# Sensor_Board_0x06_CO2_CCS811_v2.net
KiCad netlist of a schematic drawn in EAGLE
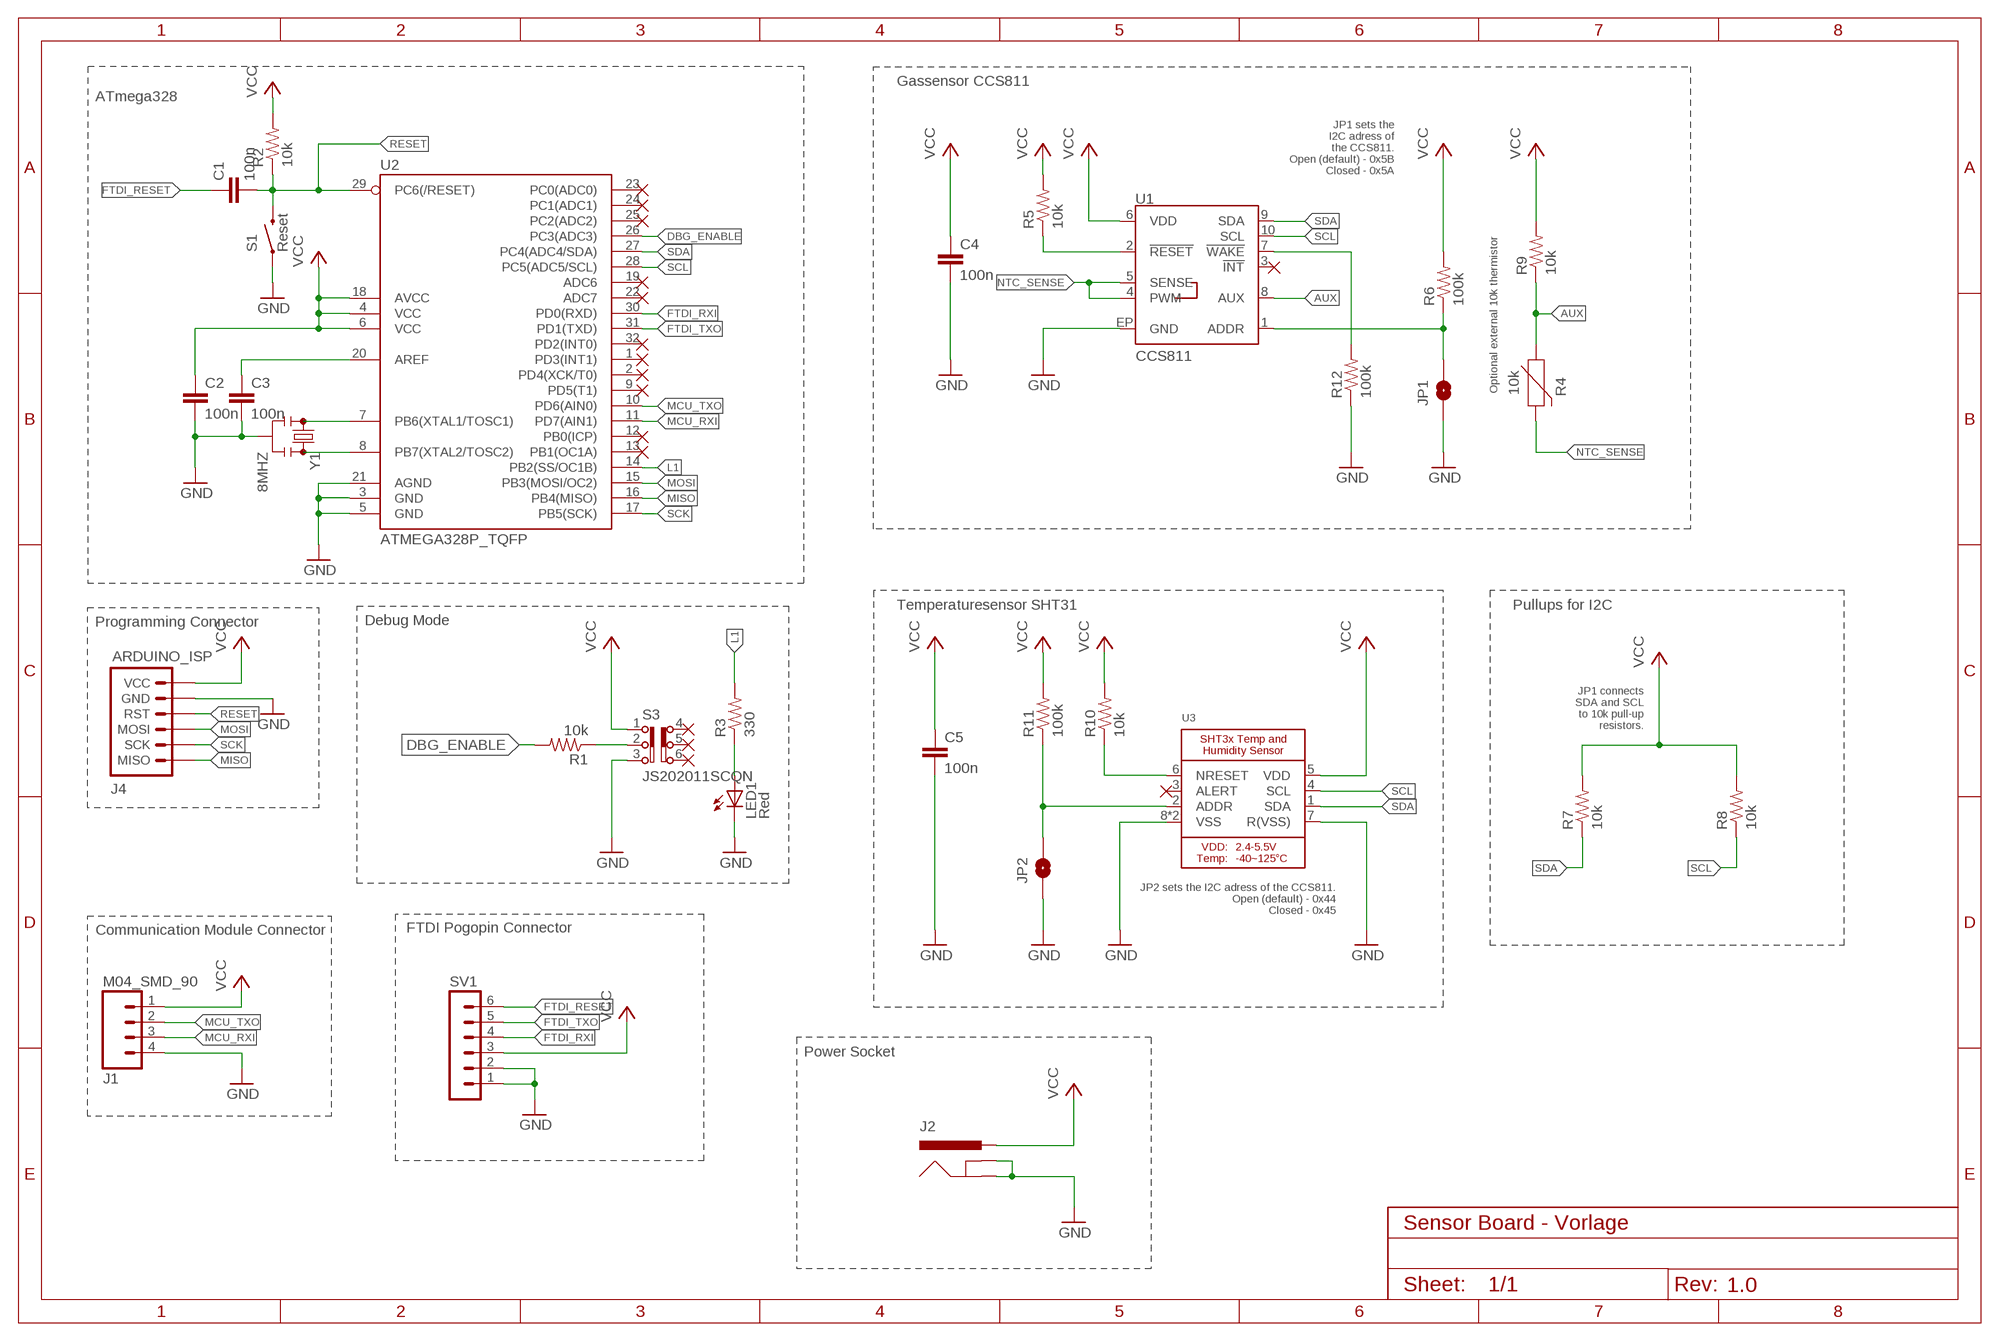
[diagram p0: schematic, sheet 1]

(export (version "E")
  (design (tool "Eeschema 10.0.6"))
  (components
    (comp (ref "C1")
      (value "100n")
      (footprint "eagle-import:C0805")
      (libsource (lib "eagle-import") (part "C"))
    )
    (comp (ref "C2")
      (value "100n")
      (footprint "eagle-import:C0805")
      (libsource (lib "eagle-import") (part "C"))
    )
    (comp (ref "C3")
      (value "100n")
      (footprint "eagle-import:C0805")
      (libsource (lib "eagle-import") (part "C"))
    )
    (comp (ref "C4")
      (value "100n")
      (footprint "eagle-import:C0805")
      (libsource (lib "eagle-import") (part "C"))
    )
    (comp (ref "C5")
      (value "100n")
      (footprint "eagle-import:C0805")
      (libsource (lib "eagle-import") (part "C"))
    )
    (comp (ref "J1")
      (value "M04_SMD_90")
      (footprint "eagle-import:M04_SMD_90")
      (libsource (lib "eagle-import") (part "M04_SMD_90"))
    )
    (comp (ref "J2")
      (value "5.5x2.1mm Barrel")
      (footprint "eagle-import:POWER_JACK_SMD")
      (libsource (lib "eagle-import") (part "POWER_JACKSMD"))
    )
    (comp (ref "J4")
      (value "ARDUINO_ISP")
      (footprint "eagle-import:M-2X3")
      (libsource (lib "eagle-import") (part "ARDUINO_ISP"))
    )
    (comp (ref "JP1")
      (value "SPARKFUN-JUMPERS_JUMPER-SMT_2_NO_SILK")
      (footprint "eagle-import:SPARKFUN-JUMPERS_SMT-JUMPER_2_NO_SILK")
      (libsource (lib "eagle-import") (part "SPARKFUN-JUMPERS_JUMPER-SMT_2_NO_SILK"))
    )
    (comp (ref "JP2")
      (value "SPARKFUN-JUMPERS_JUMPER-SMT_2_NO_SILK")
      (footprint "eagle-import:SPARKFUN-JUMPERS_SMT-JUMPER_2_NO_SILK")
      (libsource (lib "eagle-import") (part "SPARKFUN-JUMPERS_JUMPER-SMT_2_NO_SILK"))
    )
    (comp (ref "LED1")
      (value "Red")
      (footprint "eagle-import:SML0805")
      (libsource (lib "eagle-import") (part "LEDSML0805"))
    )
    (comp (ref "R1")
      (value "10k")
      (footprint "eagle-import:0805")
      (libsource (lib "eagle-import") (part "RESISTOR0805-RES"))
    )
    (comp (ref "R2")
      (value "10k")
      (footprint "eagle-import:0805")
      (libsource (lib "eagle-import") (part "RESISTOR0805-RES"))
    )
    (comp (ref "R3")
      (value "330")
      (footprint "eagle-import:0805")
      (libsource (lib "eagle-import") (part "RESISTOR0805-RES"))
    )
    (comp (ref "R4")
      (value "10k")
      (footprint "eagle-import:CCS811_BREAKOUT_TEMP_0603")
      (libsource (lib "eagle-import") (part "CCS811_BREAKOUT_TEMP_NTC-THERMISTOR-0603"))
    )
    (comp (ref "R5")
      (value "10k")
      (footprint "eagle-import:0805")
      (libsource (lib "eagle-import") (part "RESISTOR0805-RES"))
    )
    (comp (ref "R6")
      (value "100k")
      (footprint "eagle-import:0805")
      (libsource (lib "eagle-import") (part "RESISTOR0805-RES"))
    )
    (comp (ref "R7")
      (value "10k")
      (footprint "eagle-import:0805")
      (libsource (lib "eagle-import") (part "RESISTOR0805-RES"))
    )
    (comp (ref "R8")
      (value "10k")
      (footprint "eagle-import:0805")
      (libsource (lib "eagle-import") (part "RESISTOR0805-RES"))
    )
    (comp (ref "R9")
      (value "10k")
      (footprint "eagle-import:0805")
      (libsource (lib "eagle-import") (part "RESISTOR0805-RES"))
    )
    (comp (ref "R10")
      (value "10k")
      (footprint "eagle-import:0805")
      (libsource (lib "eagle-import") (part "RESISTOR0805-RES"))
    )
    (comp (ref "R11")
      (value "100k")
      (footprint "eagle-import:0805")
      (libsource (lib "eagle-import") (part "RESISTOR0805-RES"))
    )
    (comp (ref "R12")
      (value "100k")
      (footprint "eagle-import:0805")
      (libsource (lib "eagle-import") (part "RESISTOR0805-RES"))
    )
    (comp (ref "S1")
      (value "Reset")
      (footprint "eagle-import:M-PUSHBUTTON-SMD")
      (libsource (lib "eagle-import") (part "PUSHBUTTON"))
    )
    (comp (ref "S3")
      (value "JS202011SCQN")
      (footprint "eagle-import:JS202011SCQN")
      (libsource (lib "eagle-import") (part "JS202011SCQN"))
    )
    (comp (ref "SV1")
      (value "MA06-1")
      (footprint "eagle-import:MA06-1")
      (libsource (lib "eagle-import") (part "MA06-1"))
    )
    (comp (ref "U1")
      (value "CCS811")
      (footprint "eagle-import:CCS811_BREAKOUT_TEMP_LGA10")
      (libsource (lib "eagle-import") (part "CCS811_BREAKOUT_TEMP_CCS811"))
    )
    (comp (ref "U2")
      (value "ATMEGA328P_TQFP")
      (footprint "eagle-import:TQFP32-08")
      (libsource (lib "eagle-import") (part "ATMEGA328P_TQFP"))
    )
    (comp (ref "U3")
      (value "MICROBUILDER_SHT3X")
      (footprint "eagle-import:MICROBUILDER_SHT3X")
      (libsource (lib "eagle-import") (part "MICROBUILDER_SHT3X"))
    )
    (comp (ref "Y1")
      (value "8MHZ")
      (footprint "eagle-import:RESONATOR-SMD")
      (libsource (lib "eagle-import") (part "RESONATOR8MHZ"))
    )
  )
  (nets
    (net (code "1") (name "AUX") (class "Default")
      (node (ref "R4") (pin "1") (pinfunction "1_1") (pintype "bidirectional"))
      (node (ref "R9") (pin "1") (pinfunction "1_1") (pintype "passive"))
      (node (ref "U1") (pin "8") (pinfunction "AUX_8") (pintype "bidirectional"))
    )
    (net (code "2") (name "DBG_ENABLE") (class "Default")
      (node (ref "R1") (pin "2") (pinfunction "2_2") (pintype "passive"))
      (node (ref "U2") (pin "26") (pinfunction "PC3(ADC3)_26") (pintype "bidirectional"))
    )
    (net (code "3") (name "FTDI_RESET") (class "Default")
      (node (ref "C1") (pin "1") (pinfunction "1_1") (pintype "passive"))
      (node (ref "SV1") (pin "6") (pinfunction "6_6") (pintype "passive"))
    )
    (net (code "4") (name "FTDI_RXI") (class "Default")
      (node (ref "SV1") (pin "4") (pinfunction "4_4") (pintype "passive"))
      (node (ref "U2") (pin "30") (pinfunction "PD0(RXD)_30") (pintype "bidirectional"))
    )
    (net (code "5") (name "FTDI_TXO") (class "Default")
      (node (ref "SV1") (pin "5") (pinfunction "5_5") (pintype "passive"))
      (node (ref "U2") (pin "31") (pinfunction "PD1(TXD)_31") (pintype "bidirectional"))
    )
    (net (code "6") (name "GND") (class "Default")
      (node (ref "C2") (pin "2") (pinfunction "2_2") (pintype "passive"))
      (node (ref "C3") (pin "2") (pinfunction "2_2") (pintype "passive"))
      (node (ref "C4") (pin "2") (pinfunction "2_2") (pintype "passive"))
      (node (ref "C5") (pin "2") (pinfunction "2_2") (pintype "passive"))
      (node (ref "J1") (pin "4") (pinfunction "4_4") (pintype "passive"))
      (node (ref "J2") (pin "GND") (pinfunction "GNDBREAK_GND") (pintype "bidirectional"))
      (node (ref "J2") (pin "P$4") (pinfunction "GND_P$4") (pintype "bidirectional"))
      (node (ref "J4") (pin "P$5") (pinfunction "GND_P$5") (pintype "passive"))
      (node (ref "JP1") (pin "1") (pinfunction "1_1") (pintype "passive"))
      (node (ref "JP2") (pin "1") (pinfunction "1_1") (pintype "passive"))
      (node (ref "LED1") (pin "C") (pinfunction "C_C") (pintype "passive"))
      (node (ref "R12") (pin "1") (pinfunction "1_1") (pintype "passive"))
      (node (ref "S1") (pin "1") (pinfunction "LEFT_1") (pintype "passive"))
      (node (ref "S1") (pin "2") (pinfunction "LEFT_2") (pintype "passive"))
      (node (ref "S3") (pin "3") (pinfunction "3_3") (pintype "passive"))
      (node (ref "SV1") (pin "1") (pinfunction "1_1") (pintype "passive"))
      (node (ref "SV1") (pin "2") (pinfunction "2_2") (pintype "passive"))
      (node (ref "U1") (pin "EP") (pinfunction "GND_EP") (pintype "bidirectional"))
      (node (ref "U2") (pin "21") (pinfunction "AGND_21") (pintype "bidirectional"))
      (node (ref "U2") (pin "3") (pinfunction "GND_3") (pintype "bidirectional"))
      (node (ref "U2") (pin "5") (pinfunction "GND_5") (pintype "bidirectional"))
      (node (ref "U3") (pin "7") (pinfunction "R(VSS)_7") (pintype "bidirectional"))
      (node (ref "U3") (pin "8") (pinfunction "VSS_8") (pintype "power_in"))
      (node (ref "U3") (pin "THERMAL") (pinfunction "VSS_THERMAL") (pintype "power_in"))
      (node (ref "Y1") (pin "2") (pinfunction "2_2") (pintype "passive"))
    )
    (net (code "7") (name "L1") (class "Default")
      (node (ref "R3") (pin "2") (pinfunction "2_2") (pintype "passive"))
      (node (ref "U2") (pin "14") (pinfunction "PB2(SS/OC1B)_14") (pintype "bidirectional"))
    )
    (net (code "8") (name "MCU_RXI") (class "Default")
      (node (ref "J1") (pin "3") (pinfunction "3_3") (pintype "passive"))
      (node (ref "U2") (pin "11") (pinfunction "PD7(AIN1)_11") (pintype "bidirectional"))
    )
    (net (code "9") (name "MCU_TXO") (class "Default")
      (node (ref "J1") (pin "2") (pinfunction "2_2") (pintype "passive"))
      (node (ref "U2") (pin "10") (pinfunction "PD6(AIN0)_10") (pintype "bidirectional"))
    )
    (net (code "10") (name "MISO") (class "Default")
      (node (ref "J4") (pin "P$1") (pinfunction "MISO_P$1") (pintype "passive"))
      (node (ref "U2") (pin "16") (pinfunction "PB4(MISO)_16") (pintype "bidirectional"))
    )
    (net (code "11") (name "MOSI") (class "Default")
      (node (ref "J4") (pin "P$3") (pinfunction "MOSI_P$3") (pintype "passive"))
      (node (ref "U2") (pin "15") (pinfunction "PB3(MOSI/OC2)_15") (pintype "bidirectional"))
    )
    (net (code "12") (name "NTC_SENSE") (class "Default")
      (node (ref "R4") (pin "2") (pinfunction "2_2") (pintype "bidirectional"))
      (node (ref "U1") (pin "4") (pinfunction "PWM_4") (pintype "bidirectional"))
      (node (ref "U1") (pin "5") (pinfunction "SENSE_5") (pintype "bidirectional"))
    )
    (net (code "13") (name "Net-(LED1-PadA)") (class "Default")
      (node (ref "LED1") (pin "A") (pinfunction "A_A") (pintype "passive"))
      (node (ref "R3") (pin "1") (pinfunction "1_1") (pintype "passive"))
    )
    (net (code "14") (name "Net-(R1-Pad1)") (class "Default")
      (node (ref "R1") (pin "1") (pinfunction "1_1") (pintype "passive"))
      (node (ref "S3") (pin "2") (pinfunction "2_2") (pintype "passive"))
    )
    (net (code "15") (name "Net-(U1-ADDR)") (class "Default")
      (node (ref "JP1") (pin "2") (pinfunction "2_2") (pintype "passive"))
      (node (ref "R6") (pin "1") (pinfunction "1_1") (pintype "passive"))
      (node (ref "U1") (pin "1") (pinfunction "ADDR_1") (pintype "bidirectional"))
    )
    (net (code "16") (name "Net-(U1-~{RESET})") (class "Default")
      (node (ref "R5") (pin "1") (pinfunction "1_1") (pintype "passive"))
      (node (ref "U1") (pin "2") (pinfunction "~{RESET}_2") (pintype "bidirectional"))
    )
    (net (code "17") (name "Net-(U1-~{WAKE})") (class "Default")
      (node (ref "R12") (pin "2") (pinfunction "2_2") (pintype "passive"))
      (node (ref "U1") (pin "7") (pinfunction "~{WAKE}_7") (pintype "bidirectional"))
    )
    (net (code "18") (name "Net-(U2-AREF)") (class "Default")
      (node (ref "C3") (pin "1") (pinfunction "1_1") (pintype "passive"))
      (node (ref "U2") (pin "20") (pinfunction "AREF_20") (pintype "bidirectional"))
    )
    (net (code "19") (name "Net-(U2-PB6(XTAL1{slash}TOSC1))") (class "Default")
      (node (ref "U2") (pin "7") (pinfunction "PB6(XTAL1/TOSC1)_7") (pintype "bidirectional"))
      (node (ref "Y1") (pin "1") (pinfunction "1_1") (pintype "passive"))
    )
    (net (code "20") (name "Net-(U2-PB7(XTAL2{slash}TOSC2))") (class "Default")
      (node (ref "U2") (pin "8") (pinfunction "PB7(XTAL2/TOSC2)_8") (pintype "bidirectional"))
      (node (ref "Y1") (pin "3") (pinfunction "3_3") (pintype "passive"))
    )
    (net (code "21") (name "Net-(U3-ADDR)") (class "Default")
      (node (ref "JP2") (pin "2") (pinfunction "2_2") (pintype "passive"))
      (node (ref "R11") (pin "1") (pinfunction "1_1") (pintype "passive"))
      (node (ref "U3") (pin "2") (pinfunction "ADDR_2") (pintype "bidirectional"))
    )
    (net (code "22") (name "Net-(U3-NRESET)") (class "Default")
      (node (ref "R10") (pin "1") (pinfunction "1_1") (pintype "passive"))
      (node (ref "U3") (pin "6") (pinfunction "NRESET_6") (pintype "bidirectional"))
    )
    (net (code "23") (name "RESET") (class "Default")
      (node (ref "C1") (pin "2") (pinfunction "2_2") (pintype "passive"))
      (node (ref "J4") (pin "P$4") (pinfunction "RST_P$4") (pintype "passive"))
      (node (ref "R2") (pin "1") (pinfunction "1_1") (pintype "passive"))
      (node (ref "S1") (pin "3") (pinfunction "RIGHT_3") (pintype "passive"))
      (node (ref "S1") (pin "4") (pinfunction "RIGHT_4") (pintype "passive"))
      (node (ref "U2") (pin "29") (pinfunction "PC6(/RESET)_29") (pintype "bidirectional"))
    )
    (net (code "24") (name "SCK") (class "Default")
      (node (ref "J4") (pin "P$2") (pinfunction "SCK_P$2") (pintype "passive"))
      (node (ref "U2") (pin "17") (pinfunction "PB5(SCK)_17") (pintype "bidirectional"))
    )
    (net (code "25") (name "SCL") (class "Default")
      (node (ref "R8") (pin "1") (pinfunction "1_1") (pintype "passive"))
      (node (ref "U1") (pin "10") (pinfunction "SCL_10") (pintype "bidirectional"))
      (node (ref "U2") (pin "28") (pinfunction "PC5(ADC5/SCL)_28") (pintype "bidirectional"))
      (node (ref "U3") (pin "4") (pinfunction "SCL_4") (pintype "bidirectional"))
    )
    (net (code "26") (name "SDA") (class "Default")
      (node (ref "R7") (pin "1") (pinfunction "1_1") (pintype "passive"))
      (node (ref "U1") (pin "9") (pinfunction "SDA_9") (pintype "bidirectional"))
      (node (ref "U2") (pin "27") (pinfunction "PC4(ADC4/SDA)_27") (pintype "bidirectional"))
      (node (ref "U3") (pin "1") (pinfunction "SDA_1") (pintype "bidirectional"))
    )
    (net (code "27") (name "VCC") (class "Default")
      (node (ref "C2") (pin "1") (pinfunction "1_1") (pintype "passive"))
      (node (ref "C4") (pin "1") (pinfunction "1_1") (pintype "passive"))
      (node (ref "C5") (pin "1") (pinfunction "1_1") (pintype "passive"))
      (node (ref "J1") (pin "1") (pinfunction "1_1") (pintype "passive"))
      (node (ref "J2") (pin "VIN0") (pinfunction "PWR_VIN0") (pintype "bidirectional"))
      (node (ref "J2") (pin "VIN1") (pinfunction "PWR_VIN1") (pintype "bidirectional"))
      (node (ref "J4") (pin "P$6") (pinfunction "VCC_P$6") (pintype "passive"))
      (node (ref "R10") (pin "2") (pinfunction "2_2") (pintype "passive"))
      (node (ref "R11") (pin "2") (pinfunction "2_2") (pintype "passive"))
      (node (ref "R2") (pin "2") (pinfunction "2_2") (pintype "passive"))
      (node (ref "R5") (pin "2") (pinfunction "2_2") (pintype "passive"))
      (node (ref "R6") (pin "2") (pinfunction "2_2") (pintype "passive"))
      (node (ref "R7") (pin "2") (pinfunction "2_2") (pintype "passive"))
      (node (ref "R8") (pin "2") (pinfunction "2_2") (pintype "passive"))
      (node (ref "R9") (pin "2") (pinfunction "2_2") (pintype "passive"))
      (node (ref "S3") (pin "1") (pinfunction "1_1") (pintype "passive"))
      (node (ref "SV1") (pin "3") (pinfunction "3_3") (pintype "passive"))
      (node (ref "U1") (pin "6") (pinfunction "VDD_6") (pintype "bidirectional"))
      (node (ref "U2") (pin "18") (pinfunction "AVCC_18") (pintype "bidirectional"))
      (node (ref "U2") (pin "4") (pinfunction "VCC_4") (pintype "bidirectional"))
      (node (ref "U2") (pin "6") (pinfunction "VCC_6") (pintype "bidirectional"))
      (node (ref "U3") (pin "5") (pinfunction "VDD_5") (pintype "power_in"))
    )
    (net (code "28") (name "unconnected-(S3-Pad4)") (class "Default")
      (node (ref "S3") (pin "4") (pinfunction "4_4") (pintype "passive"))
    )
    (net (code "29") (name "unconnected-(S3-Pad5)") (class "Default")
      (node (ref "S3") (pin "5") (pinfunction "5_5") (pintype "passive"))
    )
    (net (code "30") (name "unconnected-(S3-Pad6)") (class "Default")
      (node (ref "S3") (pin "6") (pinfunction "6_6") (pintype "passive"))
    )
    (net (code "31") (name "unconnected-(U1-~{INT}-Pad3)") (class "Default")
      (node (ref "U1") (pin "3") (pinfunction "~{INT}_3") (pintype "bidirectional"))
    )
    (net (code "32") (name "unconnected-(U2-ADC6-Pad19)") (class "Default")
      (node (ref "U2") (pin "19") (pinfunction "ADC6_19") (pintype "bidirectional"))
    )
    (net (code "33") (name "unconnected-(U2-ADC7-Pad22)") (class "Default")
      (node (ref "U2") (pin "22") (pinfunction "ADC7_22") (pintype "bidirectional"))
    )
    (net (code "34") (name "unconnected-(U2-PB0(ICP)-Pad12)") (class "Default")
      (node (ref "U2") (pin "12") (pinfunction "PB0(ICP)_12") (pintype "bidirectional"))
    )
    (net (code "35") (name "unconnected-(U2-PB1(OC1A)-Pad13)") (class "Default")
      (node (ref "U2") (pin "13") (pinfunction "PB1(OC1A)_13") (pintype "bidirectional"))
    )
    (net (code "36") (name "unconnected-(U2-PC0(ADC0)-Pad23)") (class "Default")
      (node (ref "U2") (pin "23") (pinfunction "PC0(ADC0)_23") (pintype "bidirectional"))
    )
    (net (code "37") (name "unconnected-(U2-PC1(ADC1)-Pad24)") (class "Default")
      (node (ref "U2") (pin "24") (pinfunction "PC1(ADC1)_24") (pintype "bidirectional"))
    )
    (net (code "38") (name "unconnected-(U2-PC2(ADC2)-Pad25)") (class "Default")
      (node (ref "U2") (pin "25") (pinfunction "PC2(ADC2)_25") (pintype "bidirectional"))
    )
    (net (code "39") (name "unconnected-(U2-PD2(INT0)-Pad32)") (class "Default")
      (node (ref "U2") (pin "32") (pinfunction "PD2(INT0)_32") (pintype "bidirectional"))
    )
    (net (code "40") (name "unconnected-(U2-PD3(INT1)-Pad1)") (class "Default")
      (node (ref "U2") (pin "1") (pinfunction "PD3(INT1)_1") (pintype "bidirectional"))
    )
    (net (code "41") (name "unconnected-(U2-PD4(XCK{slash}T0)-Pad2)") (class "Default")
      (node (ref "U2") (pin "2") (pinfunction "PD4(XCK/T0)_2") (pintype "bidirectional"))
    )
    (net (code "42") (name "unconnected-(U2-PD5(T1)-Pad9)") (class "Default")
      (node (ref "U2") (pin "9") (pinfunction "PD5(T1)_9") (pintype "bidirectional"))
    )
    (net (code "43") (name "unconnected-(U3-ALERT-Pad3)") (class "Default")
      (node (ref "U3") (pin "3") (pinfunction "ALERT_3") (pintype "bidirectional"))
    )
  )
)
